# schema.net
KiCad netlist of a schematic drawn in EasyEDA
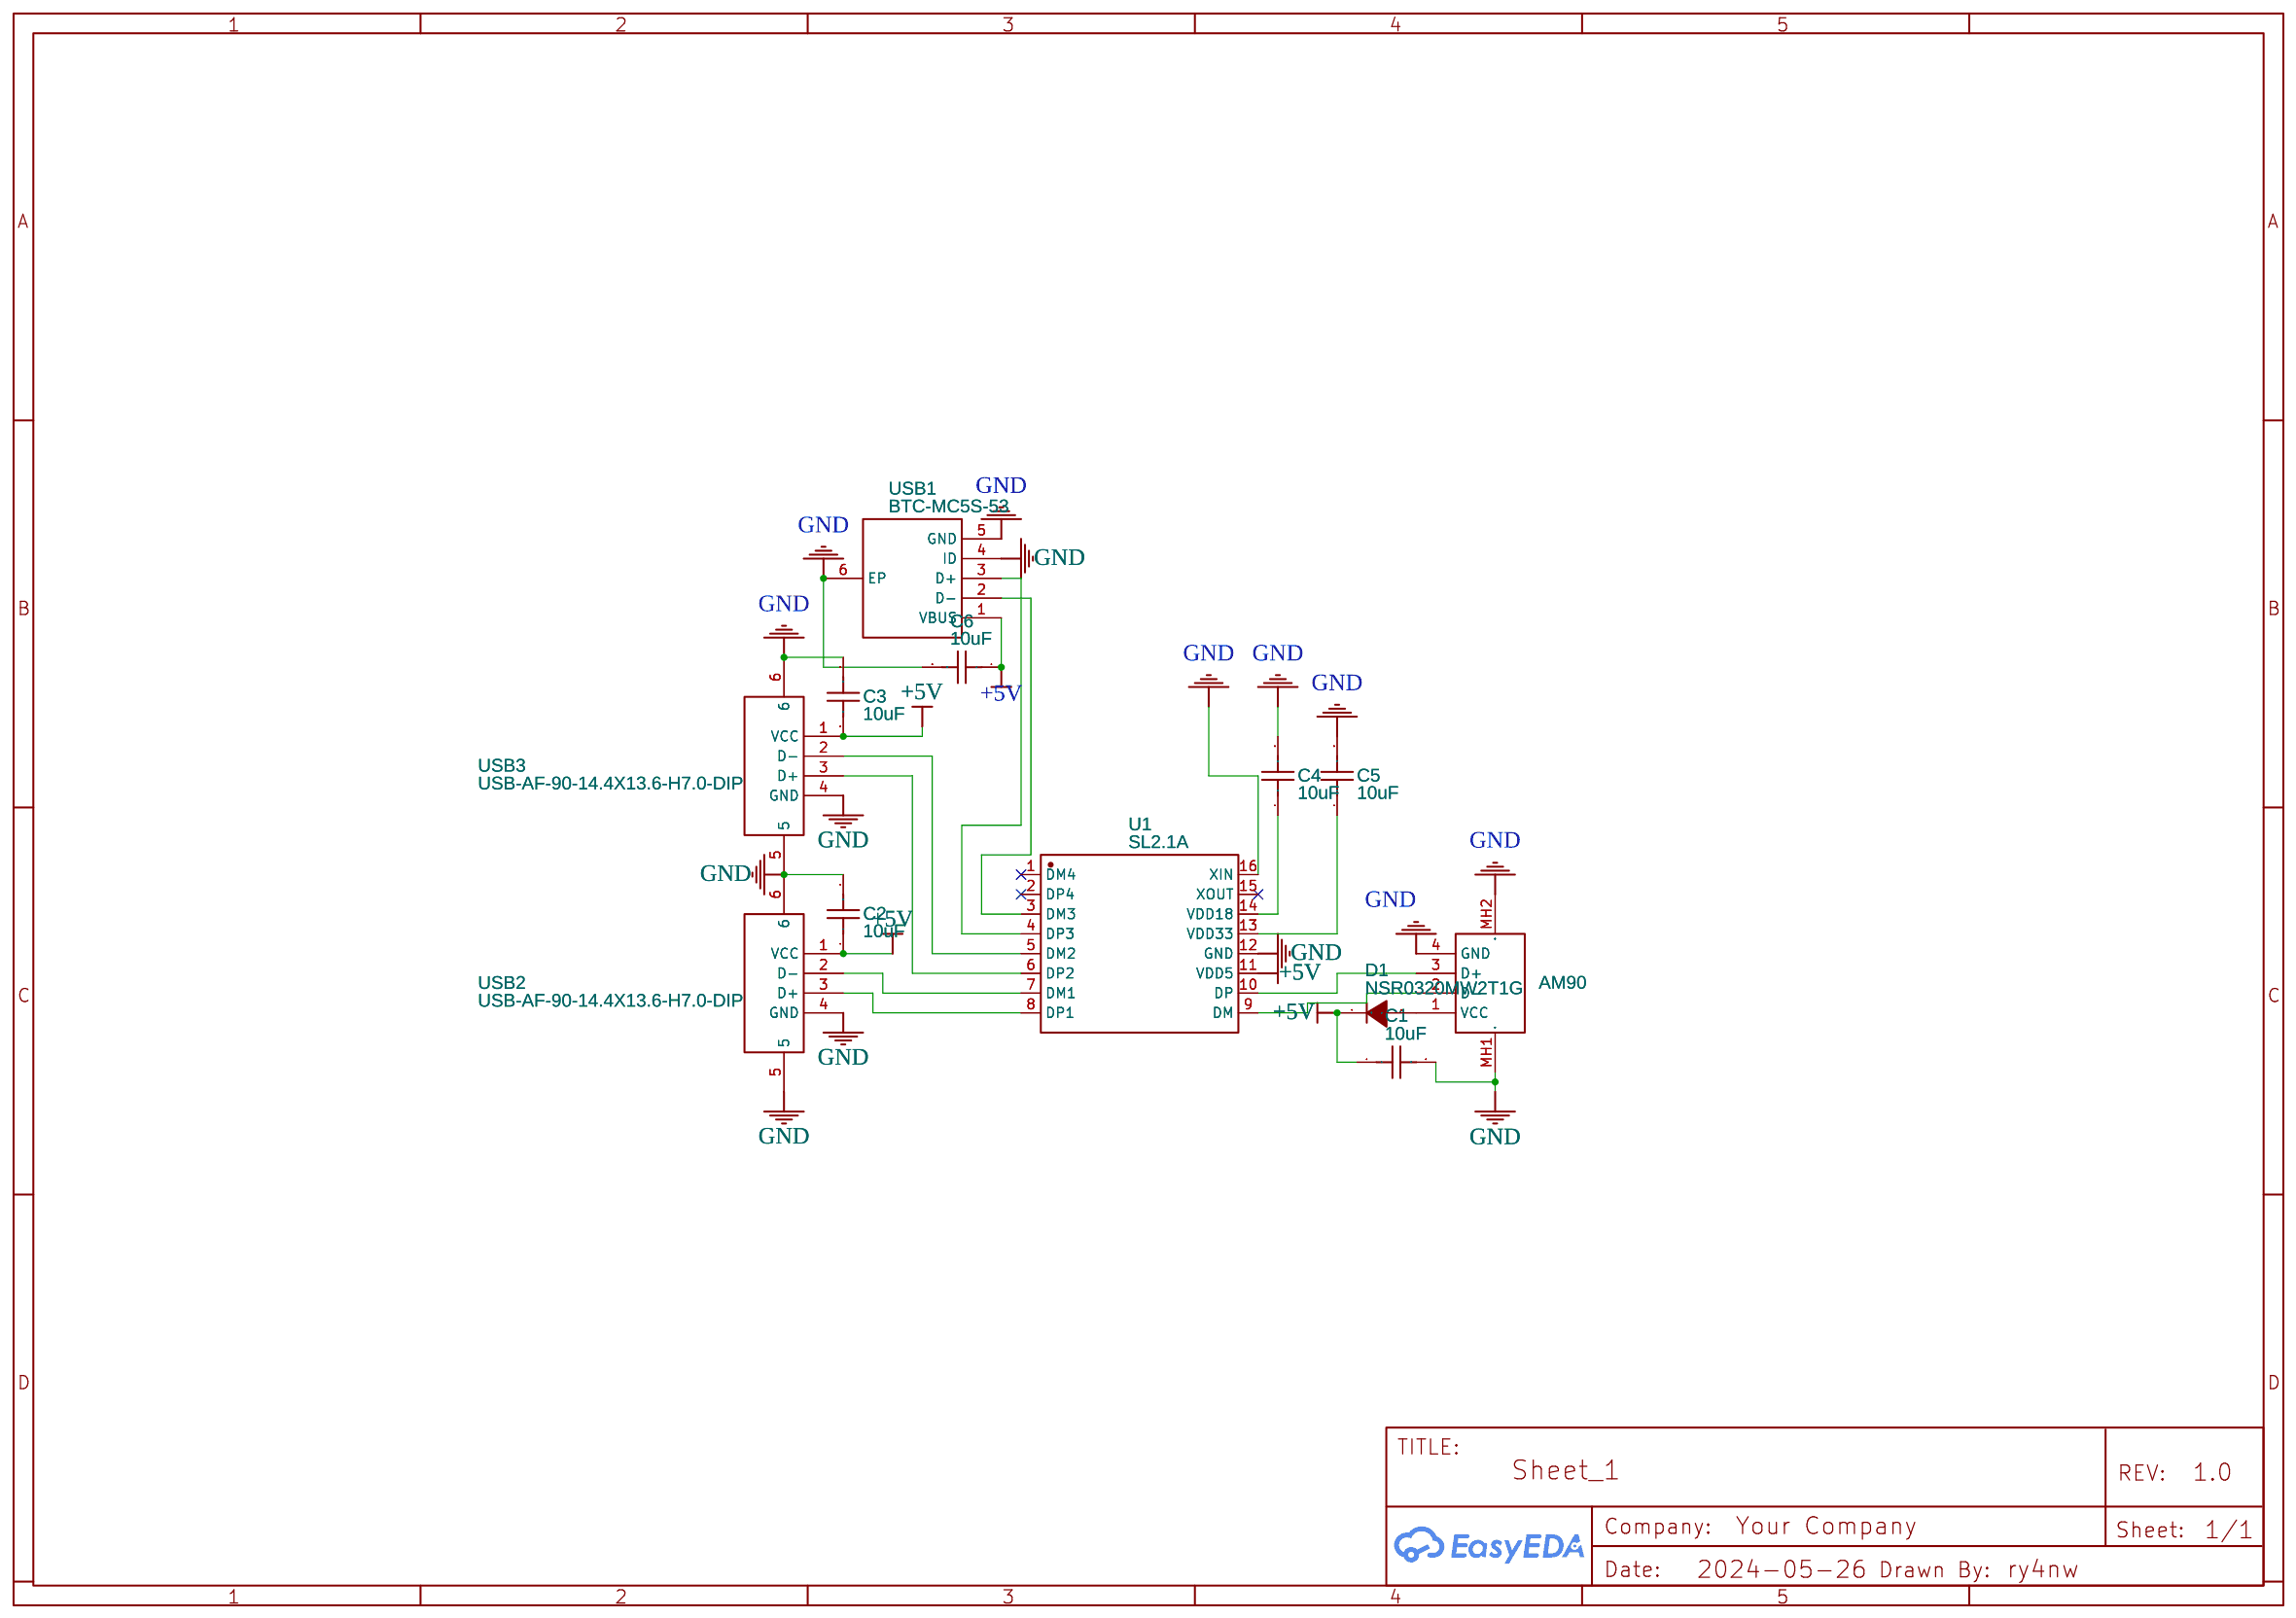
[diagram p0: schematic sheet]

(export (version "E")
  (design (tool "Eeschema 10.0.6"))
  (components
    (comp (ref "AM90")
      (value "USB-MAIN")
      (fields (field (name "Manufacturer Part") "AM90") (field (name "Manufacturer") "SHOU HAN(首韩)"))
      (libsource (lib "") (part "AM90"))
    )
    (comp (ref "C1")
      (value "10uF")
      (fields
        (field (name "Manufacturer Part") "CL10A106KP8NNNC")
        (field (name "Manufacturer") "SAMSUNG(三星)")
      )
      (libsource (lib "") (part "CL10A106KP8NNNC_2"))
    )
    (comp (ref "C2")
      (value "10uF")
      (fields
        (field (name "Manufacturer Part") "CL10A106KP8NNNC")
        (field (name "Manufacturer") "SAMSUNG(三星)")
      )
      (libsource (lib "") (part "CL10A106KP8NNNC"))
    )
    (comp (ref "C3")
      (value "10uF")
      (fields
        (field (name "Manufacturer Part") "CL10A106KP8NNNC")
        (field (name "Manufacturer") "SAMSUNG(三星)")
      )
      (libsource (lib "") (part "CL10A106KP8NNNC"))
    )
    (comp (ref "C4")
      (value "10uF")
      (fields
        (field (name "Manufacturer Part") "CL10A106KP8NNNC")
        (field (name "Manufacturer") "SAMSUNG(三星)")
      )
      (libsource (lib "") (part "CL10A106KP8NNNC"))
    )
    (comp (ref "C5")
      (value "10uF")
      (fields
        (field (name "Manufacturer Part") "CL10A106KP8NNNC")
        (field (name "Manufacturer") "SAMSUNG(三星)")
      )
      (libsource (lib "") (part "CL10A106KP8NNNC"))
    )
    (comp (ref "C6")
      (value "10uF")
      (fields
        (field (name "Manufacturer Part") "CL10A106KP8NNNC")
        (field (name "Manufacturer") "SAMSUNG(三星)")
      )
      (libsource (lib "") (part "CL10A106KP8NNNC_1"))
    )
    (comp (ref "D1")
      (value "NSR0320MW2T1G")
      (fields (field (name "Manufacturer") "onsemi(安森美)"))
      (libsource (lib "") (part "NSR0320MW2T1G"))
    )
    (comp (ref "U1")
      (value "SL2.1A")
      (fields (field (name "Manufacturer") "CoreChips(和芯润德)"))
      (libsource (lib "") (part "SL2.1A"))
    )
    (comp (ref "USB1")
      (value "BTC-MC5S-53")
      (fields (field (name "Manufacturer") "DGBZ(东莞博众)"))
      (libsource (lib "") (part "BTC-MC5S-53"))
    )
    (comp (ref "USB2")
      (value "USB-AF-90-14.4X13.6-H7.0-DIP")
      (fields (field (name "Manufacturer Part") "903-131A1011D10100") (field (name "Manufacturer") "精拓金"))
      (libsource (lib "") (part "USB-AF-90-14.4X13.6-H7.0-DIP"))
    )
    (comp (ref "USB3")
      (value "USB-AF-90-14.4X13.6-H7.0-DIP")
      (fields (field (name "Manufacturer Part") "903-131A1011D10100") (field (name "Manufacturer") "精拓金"))
      (libsource (lib "") (part "USB-AF-90-14.4X13.6-H7.0-DIP"))
    )
  )
  (nets
    (net (code "1") (name "+5V") (class "Default")
      (node (ref "C1") (pin "1") (pinfunction "1_1") (pintype "unspecified"))
      (node (ref "C2") (pin "1") (pinfunction "1_1") (pintype "unspecified"))
      (node (ref "C3") (pin "1") (pinfunction "1_1") (pintype "unspecified"))
      (node (ref "C6") (pin "1") (pinfunction "1_1") (pintype "unspecified"))
      (node (ref "D1") (pin "1") (pinfunction "C_1") (pintype "unspecified"))
      (node (ref "U1") (pin "11") (pinfunction "VDD5_11") (pintype "unspecified"))
      (node (ref "USB1") (pin "1") (pinfunction "VBUS_1") (pintype "unspecified"))
      (node (ref "USB2") (pin "1") (pinfunction "VCC_1") (pintype "unspecified"))
      (node (ref "USB3") (pin "1") (pinfunction "VCC_1") (pintype "unspecified"))
    )
    (net (code "2") (name "GND") (class "Default")
      (node (ref "AM90") (pin "4") (pinfunction "GND_4") (pintype "input"))
      (node (ref "AM90") (pin "MH1") (pinfunction "MH1_MH1") (pintype "unspecified"))
      (node (ref "AM90") (pin "MH2") (pinfunction "MH2_MH2") (pintype "unspecified"))
      (node (ref "C1") (pin "2") (pinfunction "2_2") (pintype "unspecified"))
      (node (ref "C2") (pin "2") (pinfunction "2_2") (pintype "unspecified"))
      (node (ref "C3") (pin "2") (pinfunction "2_2") (pintype "unspecified"))
      (node (ref "C4") (pin "2") (pinfunction "2_2") (pintype "unspecified"))
      (node (ref "C5") (pin "2") (pinfunction "2_2") (pintype "unspecified"))
      (node (ref "C6") (pin "2") (pinfunction "2_2") (pintype "unspecified"))
      (node (ref "U1") (pin "12") (pinfunction "GND_12") (pintype "unspecified"))
      (node (ref "U1") (pin "16") (pinfunction "XIN_16") (pintype "unspecified"))
      (node (ref "USB1") (pin "4") (pinfunction "ID_4") (pintype "unspecified"))
      (node (ref "USB1") (pin "5") (pinfunction "GND_5") (pintype "unspecified"))
      (node (ref "USB1") (pin "6") (pinfunction "EP_6") (pintype "unspecified"))
      (node (ref "USB2") (pin "4") (pinfunction "GND_4") (pintype "unspecified"))
      (node (ref "USB2") (pin "5") (pinfunction "5_5") (pintype "unspecified"))
      (node (ref "USB2") (pin "6") (pinfunction "6_6") (pintype "unspecified"))
      (node (ref "USB3") (pin "4") (pinfunction "GND_4") (pintype "unspecified"))
      (node (ref "USB3") (pin "5") (pinfunction "5_5") (pintype "unspecified"))
      (node (ref "USB3") (pin "6") (pinfunction "6_6") (pintype "unspecified"))
    )
    (net (code "3") (name "Net-(AM90-D+)") (class "Default")
      (node (ref "AM90") (pin "3") (pinfunction "D+_3") (pintype "input"))
      (node (ref "U1") (pin "10") (pinfunction "DP_10") (pintype "unspecified"))
    )
    (net (code "4") (name "Net-(AM90-D-)") (class "Default")
      (node (ref "AM90") (pin "2") (pinfunction "D-_2") (pintype "input"))
      (node (ref "U1") (pin "9") (pinfunction "DM_9") (pintype "unspecified"))
    )
    (net (code "5") (name "Net-(AM90-VCC)") (class "Default")
      (node (ref "AM90") (pin "1") (pinfunction "VCC_1") (pintype "input"))
      (node (ref "D1") (pin "2") (pinfunction "A_2") (pintype "unspecified"))
    )
    (net (code "6") (name "Net-(U1-DM1)") (class "Default")
      (node (ref "U1") (pin "7") (pinfunction "DM1_7") (pintype "unspecified"))
      (node (ref "USB2") (pin "2") (pinfunction "D-_2") (pintype "unspecified"))
    )
    (net (code "7") (name "Net-(U1-DM2)") (class "Default")
      (node (ref "U1") (pin "5") (pinfunction "DM2_5") (pintype "unspecified"))
      (node (ref "USB3") (pin "2") (pinfunction "D-_2") (pintype "unspecified"))
    )
    (net (code "8") (name "Net-(U1-DM3)") (class "Default")
      (node (ref "U1") (pin "3") (pinfunction "DM3_3") (pintype "unspecified"))
      (node (ref "USB1") (pin "2") (pinfunction "D-_2") (pintype "unspecified"))
    )
    (net (code "9") (name "Net-(U1-DP1)") (class "Default")
      (node (ref "U1") (pin "8") (pinfunction "DP1_8") (pintype "unspecified"))
      (node (ref "USB2") (pin "3") (pinfunction "D+_3") (pintype "unspecified"))
    )
    (net (code "10") (name "Net-(U1-DP2)") (class "Default")
      (node (ref "U1") (pin "6") (pinfunction "DP2_6") (pintype "unspecified"))
      (node (ref "USB3") (pin "3") (pinfunction "D+_3") (pintype "unspecified"))
    )
    (net (code "11") (name "Net-(U1-DP3)") (class "Default")
      (node (ref "U1") (pin "4") (pinfunction "DP3_4") (pintype "unspecified"))
      (node (ref "USB1") (pin "3") (pinfunction "D+_3") (pintype "unspecified"))
    )
    (net (code "12") (name "Net-(U1-VDD18)") (class "Default")
      (node (ref "C4") (pin "1") (pinfunction "1_1") (pintype "unspecified"))
      (node (ref "U1") (pin "14") (pinfunction "VDD18_14") (pintype "unspecified"))
    )
    (net (code "13") (name "Net-(U1-VDD33)") (class "Default")
      (node (ref "C5") (pin "1") (pinfunction "1_1") (pintype "unspecified"))
      (node (ref "U1") (pin "13") (pinfunction "VDD33_13") (pintype "unspecified"))
    )
    (net (code "14") (name "unconnected-(U1-DM4-Pad1)") (class "Default")
      (node (ref "U1") (pin "1") (pinfunction "DM4_1") (pintype "unspecified+no_connect"))
    )
    (net (code "15") (name "unconnected-(U1-DP4-Pad2)") (class "Default")
      (node (ref "U1") (pin "2") (pinfunction "DP4_2") (pintype "unspecified+no_connect"))
    )
    (net (code "16") (name "unconnected-(U1-XOUT-Pad15)") (class "Default")
      (node (ref "U1") (pin "15") (pinfunction "XOUT_15") (pintype "unspecified+no_connect"))
    )
  )
)
